# Pi_Wedge_B_Plus.net
KiCad netlist of a schematic drawn in EAGLE
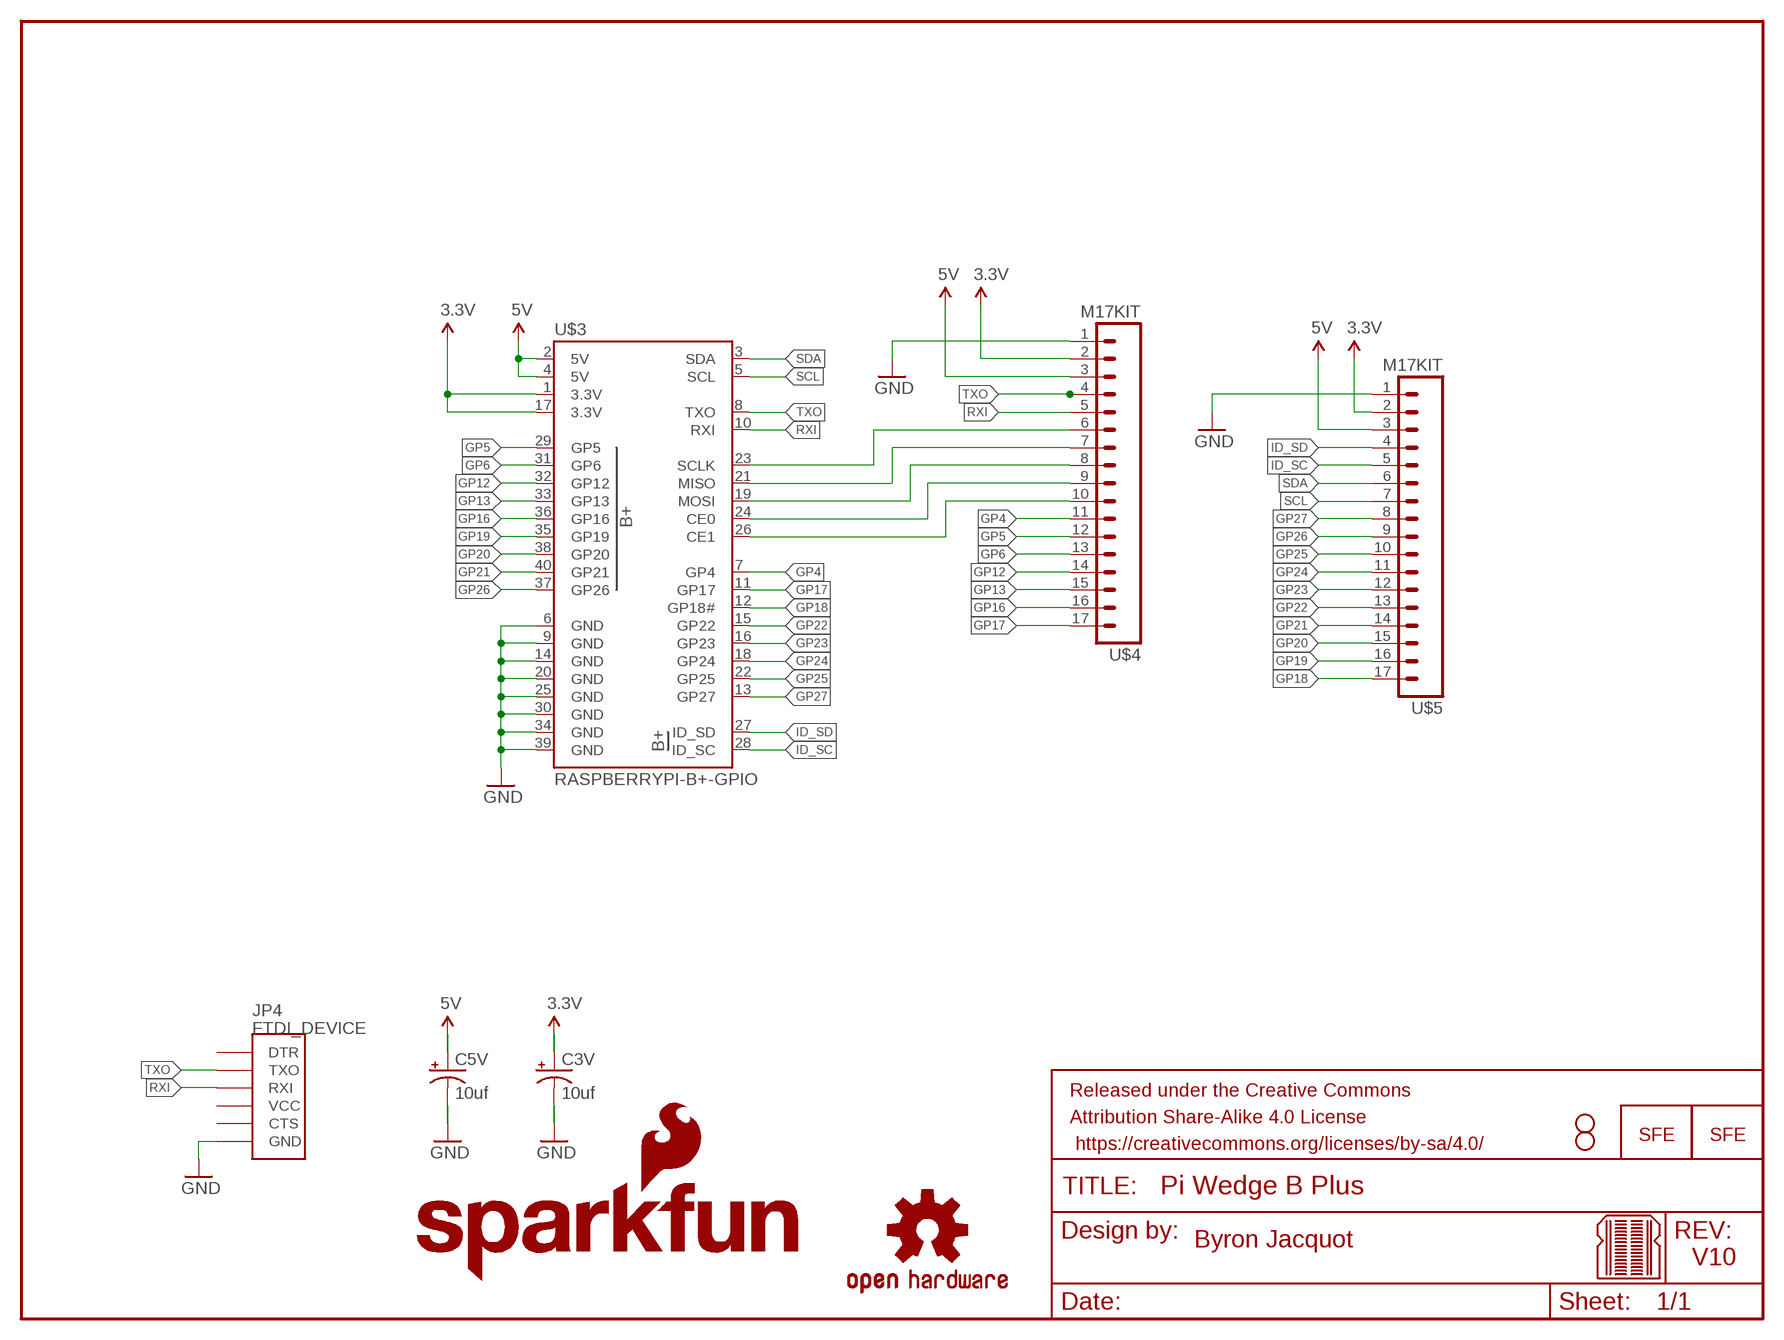
[diagram p0: schematic, sheet 1]

(export (version "E")
  (design (tool "Eeschema 10.0.6"))
  (components
    (comp (ref "C3V")
      (value "10uf")
      (footprint "eagle-import:CPOL-RADIAL-10UF-25V-KIT")
      (libsource (lib "eagle-import") (part "10UF-25V-20%(PTH)KIT"))
    )
    (comp (ref "C5V")
      (value "10uf")
      (footprint "eagle-import:CPOL-RADIAL-10UF-25V-KIT")
      (libsource (lib "eagle-import") (part "10UF-25V-20%(PTH)KIT"))
    )
    (comp (ref "FRAME2")
      (value "FRAME-LETTER")
      (footprint "eagle-import:CREATIVE_COMMONS")
      (libsource (lib "eagle-import") (part "FRAME-LETTER"))
    )
    (comp (ref "JP1")
      (value "LOGO-SFESK")
      (footprint "eagle-import:SFE-LOGO-FLAME")
      (libsource (lib "eagle-import") (part "LOGO-SFESK"))
    )
    (comp (ref "JP4")
      (value "FTDI_DEVICE")
      (footprint "eagle-import:FTDI_DEVICE_SIDE")
      (libsource (lib "eagle-import") (part "FTDI_DEVICE"))
    )
    (comp (ref "JP5")
      (value "LOGO-SFESK")
      (footprint "eagle-import:SFE-LOGO-FLAME")
      (libsource (lib "eagle-import") (part "LOGO-SFESK"))
    )
    (comp (ref "LOGO1")
      (value "SFE_LOGO_NAME_FLAME.2_INCH")
      (footprint "eagle-import:SFE_LOGO_NAME_FLAME_.2")
      (libsource (lib "eagle-import") (part "SFE_LOGO_NAME_FLAME.2_INCH"))
    )
    (comp (ref "LOGO2")
      (value "SFE_LOGO_NAME_FLAME.2_INCH")
      (footprint "eagle-import:SFE_LOGO_NAME_FLAME_.2")
      (libsource (lib "eagle-import") (part "SFE_LOGO_NAME_FLAME.2_INCH"))
    )
    (comp (ref "STANDOFF1")
      (value "STAND-OFF")
      (footprint "eagle-import:STAND-OFF")
      (libsource (lib "eagle-import") (part "STAND-OFF"))
    )
    (comp (ref "STANDOFF2")
      (value "STAND-OFF")
      (footprint "eagle-import:STAND-OFF")
      (libsource (lib "eagle-import") (part "STAND-OFF"))
    )
    (comp (ref "U$1")
      (value "OSHW-LOGOS")
      (footprint "eagle-import:OSHW-LOGO-S")
      (libsource (lib "eagle-import") (part "OSHW-LOGOS"))
    )
    (comp (ref "U$2")
      (value "BREADBOARD_PATTERN")
      (footprint "eagle-import:BREADBOARD_SPACING")
      (libsource (lib "eagle-import") (part "BREADBOARD_PATTERN"))
    )
    (comp (ref "U$3")
      (value "RASPBERRYPI-B+-GPIO")
      (footprint "eagle-import:2X20-SHROUDED")
      (libsource (lib "eagle-import") (part "RASPBERRYPI-B+-GPIO"))
    )
    (comp (ref "U$4")
      (value "M17KIT")
      (footprint "eagle-import:1X17_NO_SILK_KIT")
      (libsource (lib "eagle-import") (part "M17KIT"))
    )
    (comp (ref "U$5")
      (value "M17KIT")
      (footprint "eagle-import:1X17_NO_SILK_KIT")
      (libsource (lib "eagle-import") (part "M17KIT"))
    )
  )
  (nets
    (net (code "1") (name "3.3V") (class "Default")
      (node (ref "C3V") (pin "1") (pinfunction "+_1") (pintype "passive"))
      (node (ref "U$3") (pin "1") (pinfunction "3.3V_1") (pintype "power_in"))
      (node (ref "U$3") (pin "17") (pinfunction "3.3V_17") (pintype "power_in"))
      (node (ref "U$4") (pin "2") (pinfunction "2_2") (pintype "passive"))
      (node (ref "U$5") (pin "2") (pinfunction "2_2") (pintype "passive"))
    )
    (net (code "2") (name "5V") (class "Default")
      (node (ref "C5V") (pin "1") (pinfunction "+_1") (pintype "passive"))
      (node (ref "U$3") (pin "2") (pinfunction "5V_2") (pintype "power_in"))
      (node (ref "U$3") (pin "4") (pinfunction "5V_4") (pintype "power_in"))
      (node (ref "U$4") (pin "3") (pinfunction "3_3") (pintype "passive"))
      (node (ref "U$5") (pin "3") (pinfunction "3_3") (pintype "passive"))
    )
    (net (code "3") (name "GND") (class "Default")
      (node (ref "C3V") (pin "2") (pinfunction "-_2") (pintype "passive"))
      (node (ref "C5V") (pin "2") (pinfunction "-_2") (pintype "passive"))
      (node (ref "JP4") (pin "P$6") (pinfunction "GND_P$6") (pintype "bidirectional"))
      (node (ref "U$3") (pin "14") (pinfunction "GND_14") (pintype "power_in"))
      (node (ref "U$3") (pin "20") (pinfunction "GND_20") (pintype "power_in"))
      (node (ref "U$3") (pin "25") (pinfunction "GND_25") (pintype "power_in"))
      (node (ref "U$3") (pin "30") (pinfunction "GND_30") (pintype "power_in"))
      (node (ref "U$3") (pin "34") (pinfunction "GND_34") (pintype "power_in"))
      (node (ref "U$3") (pin "39") (pinfunction "GND_39") (pintype "power_in"))
      (node (ref "U$3") (pin "6") (pinfunction "GND_6") (pintype "power_in"))
      (node (ref "U$3") (pin "9") (pinfunction "GND_9") (pintype "power_in"))
      (node (ref "U$4") (pin "1") (pinfunction "1_1") (pintype "passive"))
      (node (ref "U$5") (pin "1") (pinfunction "1_1") (pintype "passive"))
    )
    (net (code "4") (name "GP4") (class "Default")
      (node (ref "U$3") (pin "7") (pinfunction "GP4_7") (pintype "bidirectional"))
      (node (ref "U$4") (pin "11") (pinfunction "11_11") (pintype "passive"))
    )
    (net (code "5") (name "GP5") (class "Default")
      (node (ref "U$3") (pin "29") (pinfunction "GP5_29") (pintype "bidirectional"))
      (node (ref "U$4") (pin "12") (pinfunction "12_12") (pintype "passive"))
    )
    (net (code "6") (name "GP6") (class "Default")
      (node (ref "U$3") (pin "31") (pinfunction "GP6_31") (pintype "bidirectional"))
      (node (ref "U$4") (pin "13") (pinfunction "13_13") (pintype "passive"))
    )
    (net (code "7") (name "GP12") (class "Default")
      (node (ref "U$3") (pin "32") (pinfunction "GP12_32") (pintype "bidirectional"))
      (node (ref "U$4") (pin "14") (pinfunction "14_14") (pintype "passive"))
    )
    (net (code "8") (name "GP13") (class "Default")
      (node (ref "U$3") (pin "33") (pinfunction "GP13_33") (pintype "bidirectional"))
      (node (ref "U$4") (pin "15") (pinfunction "15_15") (pintype "passive"))
    )
    (net (code "9") (name "GP16") (class "Default")
      (node (ref "U$3") (pin "36") (pinfunction "GP16_36") (pintype "bidirectional"))
      (node (ref "U$4") (pin "16") (pinfunction "16_16") (pintype "passive"))
    )
    (net (code "10") (name "GP17") (class "Default")
      (node (ref "U$3") (pin "11") (pinfunction "GP17_11") (pintype "bidirectional"))
      (node (ref "U$4") (pin "17") (pinfunction "17_17") (pintype "passive"))
    )
    (net (code "11") (name "GP18") (class "Default")
      (node (ref "U$3") (pin "12") (pinfunction "GP18#_12") (pintype "bidirectional"))
      (node (ref "U$5") (pin "17") (pinfunction "17_17") (pintype "passive"))
    )
    (net (code "12") (name "GP19") (class "Default")
      (node (ref "U$3") (pin "35") (pinfunction "GP19_35") (pintype "bidirectional"))
      (node (ref "U$5") (pin "16") (pinfunction "16_16") (pintype "passive"))
    )
    (net (code "13") (name "GP20") (class "Default")
      (node (ref "U$3") (pin "38") (pinfunction "GP20_38") (pintype "bidirectional"))
      (node (ref "U$5") (pin "15") (pinfunction "15_15") (pintype "passive"))
    )
    (net (code "14") (name "GP21") (class "Default")
      (node (ref "U$3") (pin "40") (pinfunction "GP21_40") (pintype "bidirectional"))
      (node (ref "U$5") (pin "14") (pinfunction "14_14") (pintype "passive"))
    )
    (net (code "15") (name "GP22") (class "Default")
      (node (ref "U$3") (pin "15") (pinfunction "GP22_15") (pintype "bidirectional"))
      (node (ref "U$5") (pin "13") (pinfunction "13_13") (pintype "passive"))
    )
    (net (code "16") (name "GP23") (class "Default")
      (node (ref "U$3") (pin "16") (pinfunction "GP23_16") (pintype "bidirectional"))
      (node (ref "U$5") (pin "12") (pinfunction "12_12") (pintype "passive"))
    )
    (net (code "17") (name "GP24") (class "Default")
      (node (ref "U$3") (pin "18") (pinfunction "GP24_18") (pintype "bidirectional"))
      (node (ref "U$5") (pin "11") (pinfunction "11_11") (pintype "passive"))
    )
    (net (code "18") (name "GP25") (class "Default")
      (node (ref "U$3") (pin "22") (pinfunction "GP25_22") (pintype "bidirectional"))
      (node (ref "U$5") (pin "10") (pinfunction "10_10") (pintype "passive"))
    )
    (net (code "19") (name "GP26") (class "Default")
      (node (ref "U$3") (pin "37") (pinfunction "GP26_37") (pintype "bidirectional"))
      (node (ref "U$5") (pin "9") (pinfunction "9_9") (pintype "passive"))
    )
    (net (code "20") (name "GP27") (class "Default")
      (node (ref "U$3") (pin "13") (pinfunction "GP27_13") (pintype "bidirectional"))
      (node (ref "U$5") (pin "8") (pinfunction "8_8") (pintype "passive"))
    )
    (net (code "21") (name "ID_SC") (class "Default")
      (node (ref "U$3") (pin "28") (pinfunction "ID_SC_28") (pintype "bidirectional"))
      (node (ref "U$5") (pin "5") (pinfunction "5_5") (pintype "passive"))
    )
    (net (code "22") (name "ID_SD") (class "Default")
      (node (ref "U$3") (pin "27") (pinfunction "ID_SD_27") (pintype "bidirectional"))
      (node (ref "U$5") (pin "4") (pinfunction "4_4") (pintype "passive"))
    )
    (net (code "23") (name "Net-(U$3-CE0)") (class "Default")
      (node (ref "U$3") (pin "24") (pinfunction "CE0_24") (pintype "output"))
      (node (ref "U$4") (pin "9") (pinfunction "9_9") (pintype "passive"))
    )
    (net (code "24") (name "Net-(U$3-CE1)") (class "Default")
      (node (ref "U$3") (pin "26") (pinfunction "CE1_26") (pintype "output"))
      (node (ref "U$4") (pin "10") (pinfunction "10_10") (pintype "passive"))
    )
    (net (code "25") (name "Net-(U$3-MISO)") (class "Default")
      (node (ref "U$3") (pin "21") (pinfunction "MISO_21") (pintype "input"))
      (node (ref "U$4") (pin "7") (pinfunction "7_7") (pintype "passive"))
    )
    (net (code "26") (name "Net-(U$3-MOSI)") (class "Default")
      (node (ref "U$3") (pin "19") (pinfunction "MOSI_19") (pintype "output"))
      (node (ref "U$4") (pin "8") (pinfunction "8_8") (pintype "passive"))
    )
    (net (code "27") (name "Net-(U$3-SCLK)") (class "Default")
      (node (ref "U$3") (pin "23") (pinfunction "SCLK_23") (pintype "output"))
      (node (ref "U$4") (pin "6") (pinfunction "6_6") (pintype "passive"))
    )
    (net (code "28") (name "RXI") (class "Default")
      (node (ref "JP4") (pin "P$3") (pinfunction "RXI_P$3") (pintype "bidirectional"))
      (node (ref "U$3") (pin "10") (pinfunction "RXI_10") (pintype "input"))
      (node (ref "U$4") (pin "5") (pinfunction "5_5") (pintype "passive"))
    )
    (net (code "29") (name "SCL") (class "Default")
      (node (ref "U$3") (pin "5") (pinfunction "SCL_5") (pintype "bidirectional"))
      (node (ref "U$5") (pin "7") (pinfunction "7_7") (pintype "passive"))
    )
    (net (code "30") (name "SDA") (class "Default")
      (node (ref "U$3") (pin "3") (pinfunction "SDA_3") (pintype "bidirectional"))
      (node (ref "U$5") (pin "6") (pinfunction "6_6") (pintype "passive"))
    )
    (net (code "31") (name "TXO") (class "Default")
      (node (ref "JP4") (pin "P$2") (pinfunction "TXO_P$2") (pintype "bidirectional"))
      (node (ref "U$3") (pin "8") (pinfunction "TXO_8") (pintype "output"))
      (node (ref "U$4") (pin "4") (pinfunction "4_4") (pintype "passive"))
    )
    (net (code "32") (name "unconnected-(JP4-CTS-PadP$5)") (class "Default")
      (node (ref "JP4") (pin "P$5") (pinfunction "CTS_P$5") (pintype "bidirectional"))
    )
    (net (code "33") (name "unconnected-(JP4-DTR-PadP$1)") (class "Default")
      (node (ref "JP4") (pin "P$1") (pinfunction "DTR_P$1") (pintype "bidirectional"))
    )
    (net (code "34") (name "unconnected-(JP4-VCC-PadP$4)") (class "Default")
      (node (ref "JP4") (pin "P$4") (pinfunction "VCC_P$4") (pintype "bidirectional"))
    )
  )
)
